# Charger.net
KiCad netlist of a schematic drawn in Altium Designer
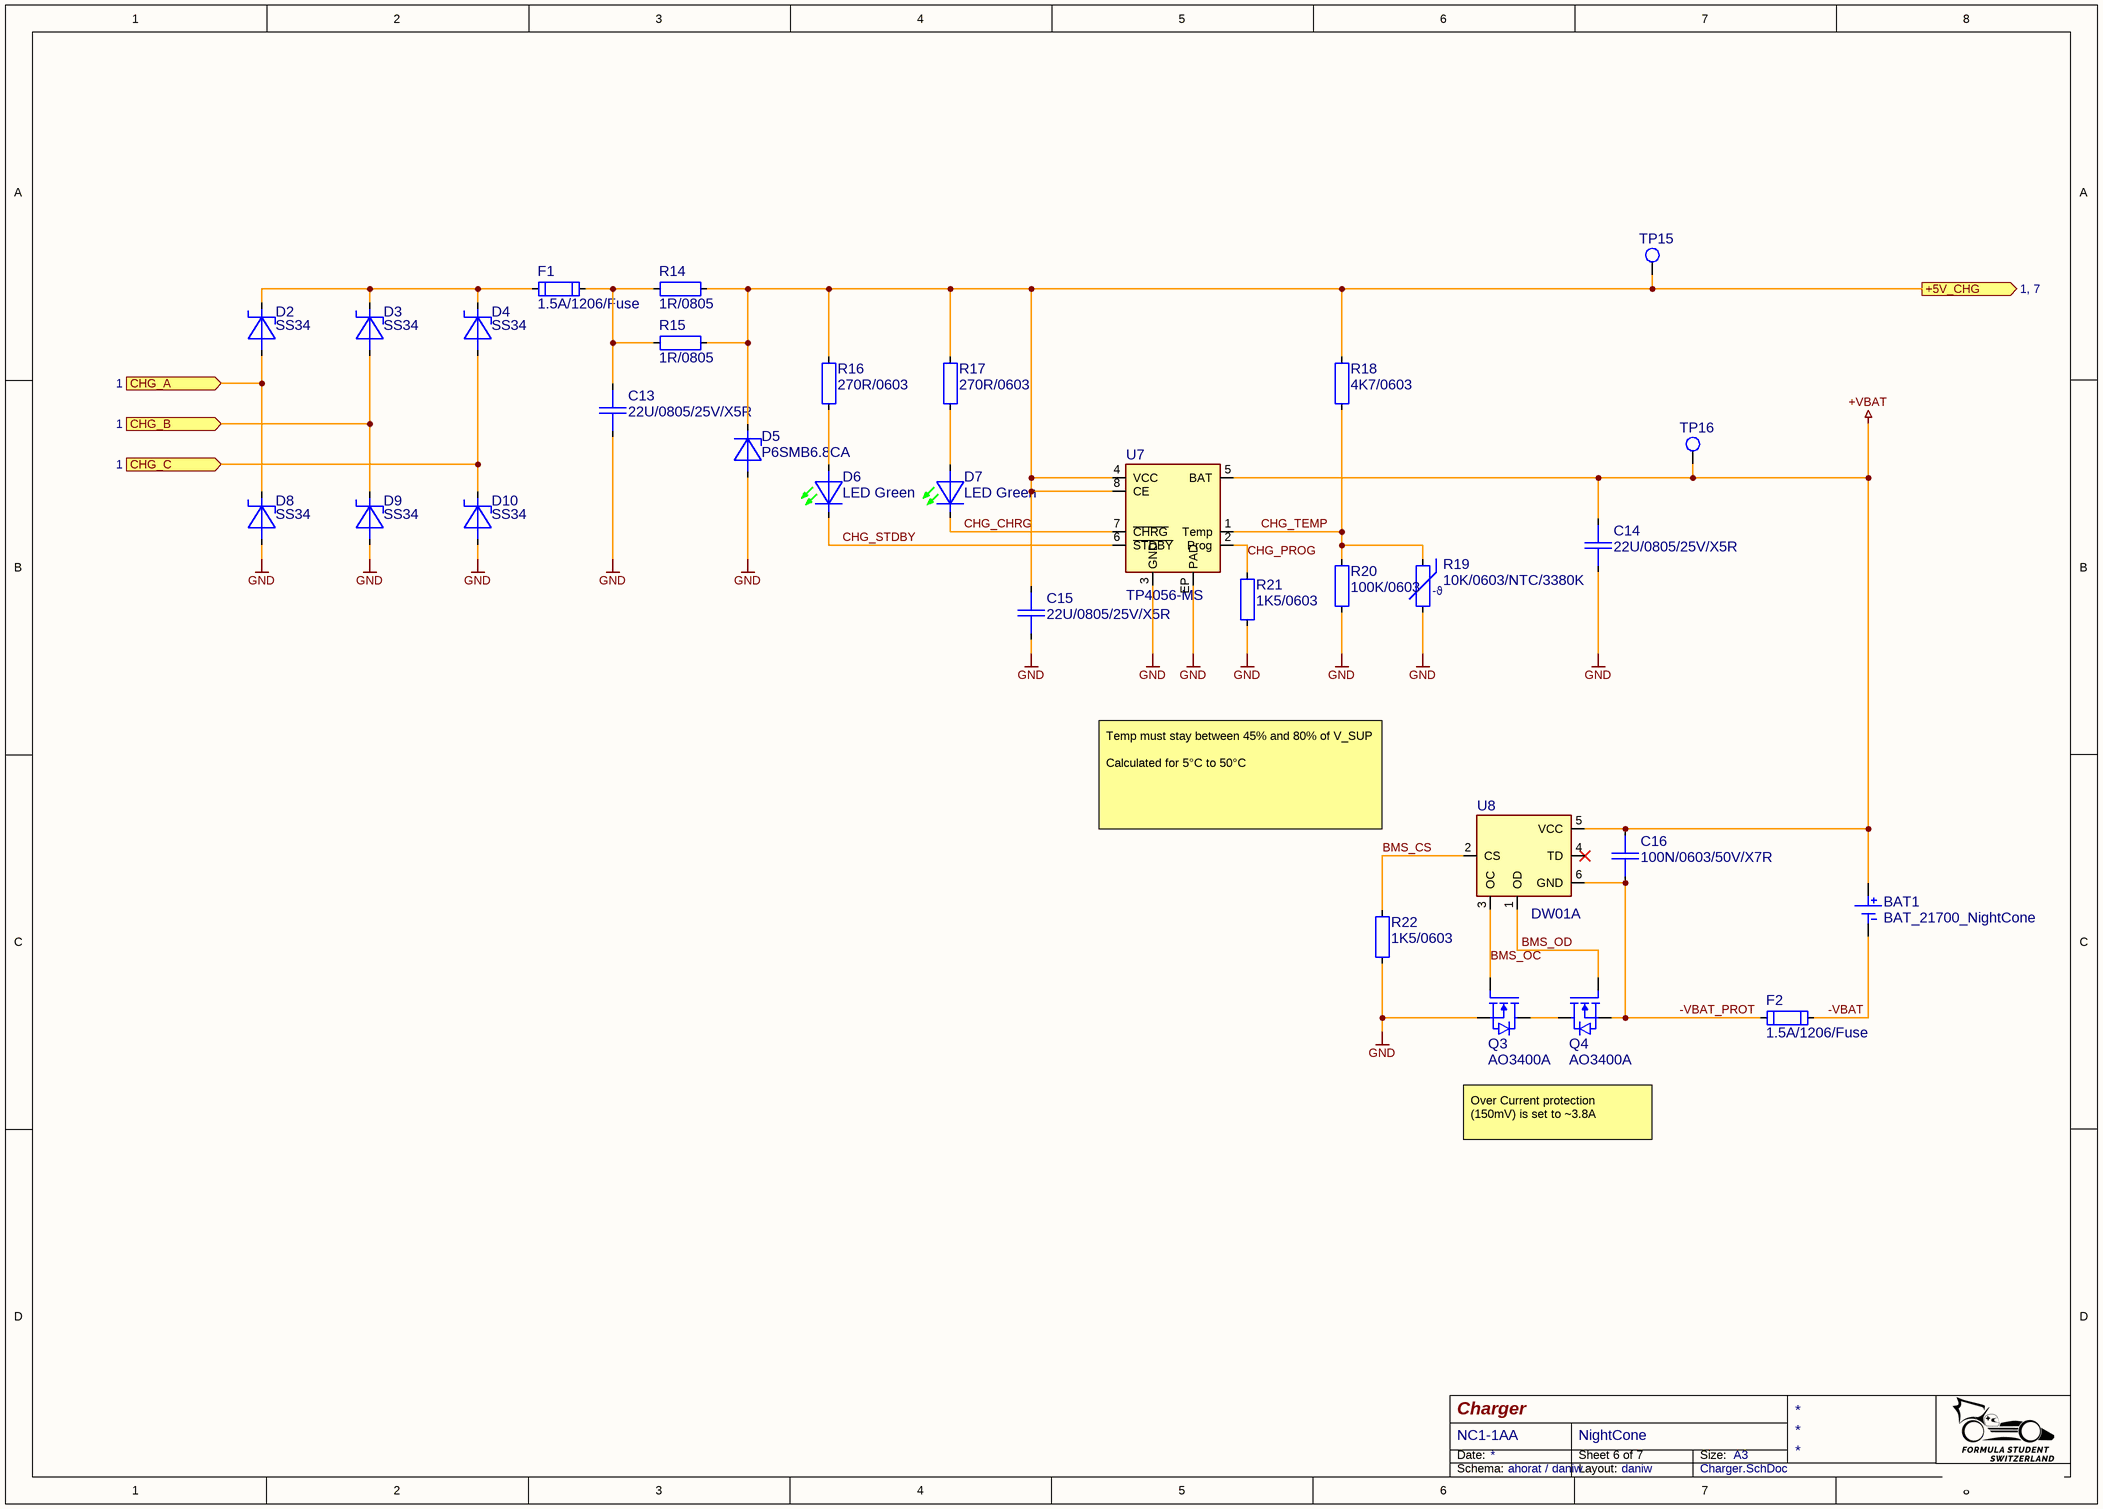
[diagram p0: Charger.SchDoc]

(export (version "E")
  (design (tool "Eeschema 10.0.6"))
  (components
    (comp (ref "BAT1")
      (value "BAT_21700_NightCone")
      (footprint "BAT-21700-NC")
      (description "21700 Battery cell for FSCH nightcone project")
      (fields (field (name "MANUFACTURER") "NONE"))
      (libsource (lib "daniw_altium_lib") (part "Battery_1"))
    )
    (comp (ref "C13")
      (value "22U/0805/25V/X5R")
      (footprint "CAP0805_X7R")
      (description "CAP SM 0805 22uF 25V X5R")
      (fields (field (name "MANUFACTURER") "GENERIC"))
      (libsource (lib "daniw_altium_lib") (part "C"))
    )
    (comp (ref "C14")
      (value "22U/0805/25V/X5R")
      (footprint "CAP0805_X7R")
      (description "CAP SM 0805 22uF 25V X5R")
      (fields (field (name "MANUFACTURER") "GENERIC"))
      (libsource (lib "daniw_altium_lib") (part "C"))
    )
    (comp (ref "C15")
      (value "22U/0805/25V/X5R")
      (footprint "CAP0805_X7R")
      (description "CAP SM 0805 22uF 25V X5R")
      (fields (field (name "MANUFACTURER") "GENERIC"))
      (libsource (lib "daniw_altium_lib") (part "C"))
    )
    (comp (ref "C16")
      (value "100N/0603/50V/X7R")
      (footprint "CAP0603_X7R")
      (description "CAP SM 0603 100nF 50V X7R")
      (fields (field (name "MANUFACTURER") "GENERIC"))
      (libsource (lib "daniw_altium_lib") (part "C"))
    )
    (comp (ref "D2")
      (value "SS34")
      (footprint "DIOM5226X230")
      (description "Si Shottky Diode 3A DO-214AC")
      (fields (field (name "MANUFACTURER") "GENERIC"))
      (libsource (lib "daniw_altium_lib") (part "D_Schottky"))
    )
    (comp (ref "D3")
      (value "SS34")
      (footprint "DIOM5226X230")
      (description "Si Shottky Diode 3A DO-214AC")
      (fields (field (name "MANUFACTURER") "GENERIC"))
      (libsource (lib "daniw_altium_lib") (part "D_Schottky"))
    )
    (comp (ref "D4")
      (value "SS34")
      (footprint "DIOM5226X230")
      (description "Si Shottky Diode 3A DO-214AC")
      (fields (field (name "MANUFACTURER") "GENERIC"))
      (libsource (lib "daniw_altium_lib") (part "D_Schottky"))
    )
    (comp (ref "D5")
      (value "P6SMB6.8CA")
      (footprint "DIOM5436X265")
      (description "10.5V 6.45V 5.8V SMB(DO-214AA) TVS")
      (fields (field (name "MANUFACTURER") "Littelfuse Inc."))
      (libsource (lib "daniw_altium_lib") (part "D_Zener"))
    )
    (comp (ref "D6")
      (value "LED Green")
      (footprint "LED0805_GREEN")
      (description "Generic LED Green 0805")
      (fields (field (name "PART NUMBER") "LED Green 0805") (field (name "MANUFACTURER") "GENERIC"))
      (libsource (lib "daniw_altium_lib") (part "LED_GREEN"))
    )
    (comp (ref "D7")
      (value "LED Green")
      (footprint "LED0805_GREEN")
      (description "Generic LED Green 0805")
      (fields (field (name "PART NUMBER") "LED Green 0805") (field (name "MANUFACTURER") "GENERIC"))
      (libsource (lib "daniw_altium_lib") (part "LED_GREEN"))
    )
    (comp (ref "D8")
      (value "SS34")
      (footprint "DIOM5226X230")
      (description "Si Shottky Diode 3A DO-214AC")
      (fields (field (name "MANUFACTURER") "GENERIC"))
      (libsource (lib "daniw_altium_lib") (part "D_Schottky"))
    )
    (comp (ref "D9")
      (value "SS34")
      (footprint "DIOM5226X230")
      (description "Si Shottky Diode 3A DO-214AC")
      (fields (field (name "MANUFACTURER") "GENERIC"))
      (libsource (lib "daniw_altium_lib") (part "D_Schottky"))
    )
    (comp (ref "D10")
      (value "SS34")
      (footprint "DIOM5226X230")
      (description "Si Shottky Diode 3A DO-214AC")
      (fields (field (name "MANUFACTURER") "GENERIC"))
      (libsource (lib "daniw_altium_lib") (part "D_Schottky"))
    )
    (comp (ref "F1")
      (value "1.5A/1206/Fuse")
      (footprint "Fuse1206-0.55-WW")
      (description "Multifuse 1206 1.5A")
      (fields (field (name "MANUFACTURER") "GENERIC"))
      (libsource (lib "daniw_altium_lib") (part "Fuse"))
    )
    (comp (ref "F2")
      (value "1.5A/1206/Fuse")
      (footprint "Fuse1206-0.55-WW")
      (description "Multifuse 1206 1.5A")
      (fields (field (name "MANUFACTURER") "GENERIC"))
      (libsource (lib "daniw_altium_lib") (part "Fuse"))
    )
    (comp (ref "Q3")
      (value "AO3400A")
      (footprint "SOT2395P280X125-3-SE")
      (description "30V N-Channel MOSFET")
      (fields (field (name "MANUFACTURER") "Alpha & Omega Semiconductor"))
      (libsource (lib "daniw_altium_lib") (part "MOSFET N_SOT23"))
    )
    (comp (ref "Q4")
      (value "AO3400A")
      (footprint "SOT2395P280X125-3-SE")
      (description "30V N-Channel MOSFET")
      (fields (field (name "MANUFACTURER") "Alpha & Omega Semiconductor"))
      (libsource (lib "daniw_altium_lib") (part "MOSFET N_SOT23"))
    )
    (comp (ref "R14")
      (value "1R/0805")
      (footprint "R0805-0.50-WW")
      (description "RES SM 0805 1R")
      (fields (field (name "MANUFACTURER") "GENERIC"))
      (libsource (lib "daniw_altium_lib") (part "R"))
    )
    (comp (ref "R15")
      (value "1R/0805")
      (footprint "R0805-0.50-WW")
      (description "RES SM 0805 1R")
      (fields (field (name "MANUFACTURER") "GENERIC"))
      (libsource (lib "daniw_altium_lib") (part "R"))
    )
    (comp (ref "R16")
      (value "270R/0603")
      (footprint "R0603-0.40-WW")
      (description "RES SM 0603 270R")
      (fields (field (name "MANUFACTURER") "GENERIC"))
      (libsource (lib "daniw_altium_lib") (part "R"))
    )
    (comp (ref "R17")
      (value "270R/0603")
      (footprint "R0603-0.40-WW")
      (description "RES SM 0603 270R")
      (fields (field (name "MANUFACTURER") "GENERIC"))
      (libsource (lib "daniw_altium_lib") (part "R"))
    )
    (comp (ref "R18")
      (value "4K7/0603")
      (footprint "R0603-0.40-WW")
      (description "RES SM 0603 4K7")
      (fields (field (name "MANUFACTURER") "GENERIC"))
      (libsource (lib "daniw_altium_lib") (part "R"))
    )
    (comp (ref "R19")
      (value "10K/0603/NTC/3380K")
      (footprint "R0603-0.40-WW")
      (description "RES NTC SM 0603 10K")
      (fields (field (name "MANUFACTURER") "GENERIC"))
      (libsource (lib "daniw_altium_lib") (part "R_NTC"))
    )
    (comp (ref "R20")
      (value "100K/0603")
      (footprint "R0603-0.40-WW")
      (description "RES SM 0603 100K")
      (fields (field (name "MANUFACTURER") "GENERIC"))
      (libsource (lib "daniw_altium_lib") (part "R"))
    )
    (comp (ref "R21")
      (value "1K5/0603")
      (footprint "R0603-0.40-WW")
      (description "RES SM 0603 1K5")
      (fields (field (name "MANUFACTURER") "GENERIC"))
      (libsource (lib "daniw_altium_lib") (part "R"))
    )
    (comp (ref "R22")
      (value "1K5/0603")
      (footprint "R0603-0.40-WW")
      (description "RES SM 0603 1K5")
      (fields (field (name "MANUFACTURER") "GENERIC"))
      (libsource (lib "daniw_altium_lib") (part "R"))
    )
    (comp (ref "TP15")
      (value "TP_THD_1.5/0.8")
      (footprint "TP_THD_1.5/0.8")
      (description "THT Test Point 1.5/0.8mm")
      (fields (field (name "MANUFACTURER") "NONE"))
      (libsource (lib "daniw_altium_lib") (part "Testpoint"))
    )
    (comp (ref "TP16")
      (value "TP_THD_1.5/0.8")
      (footprint "TP_THD_1.5/0.8")
      (description "THT Test Point 1.5/0.8mm")
      (fields (field (name "MANUFACTURER") "NONE"))
      (libsource (lib "daniw_altium_lib") (part "Testpoint"))
    )
    (comp (ref "U7")
      (value "TP4056-MS")
      (footprint "SOP127P600X155-9-TH330x240-NW")
      (description "1A Standalone Linear Li-lon Battery Charger with Thermal Regulation in SOP-8")
      (fields (field (name "MANUFACTURER") "MSKSEMI"))
      (libsource (lib "daniw_altium_lib") (part "TP4056"))
    )
    (comp (ref "U8")
      (value "DW01A")
      (footprint "SOT2395P280X125-6-SW")
      (description "Single Cell Lithium-ion battery protection IC")
      (fields (field (name "MANUFACTURER") "PUOLOP"))
      (libsource (lib "daniw_altium_lib") (part "DW01A"))
    )
  )
  (nets
    (net (code "1") (name "+VBAT") (class "Default")
      (node (ref "BAT1") (pin "1") (pinfunction "+_1") (pintype "passive"))
      (node (ref "C14") (pin "1") (pinfunction "1_1") (pintype "passive"))
      (node (ref "C16") (pin "1") (pinfunction "1_1") (pintype "passive"))
      (node (ref "TP16") (pin "1") (pinfunction "1_1") (pintype "passive"))
      (node (ref "U7") (pin "5") (pinfunction "BAT_5") (pintype "passive"))
      (node (ref "U8") (pin "5") (pinfunction "VCC_5") (pintype "passive"))
    )
    (net (code "2") (name "/+5V_CHG") (class "Default")
      (node (ref "C15") (pin "1") (pinfunction "1_1") (pintype "passive"))
      (node (ref "D5") (pin "1") (pinfunction "1_1") (pintype "passive"))
      (node (ref "R14") (pin "2") (pinfunction "2_2") (pintype "passive"))
      (node (ref "R15") (pin "2") (pinfunction "2_2") (pintype "passive"))
      (node (ref "R16") (pin "1") (pinfunction "1_1") (pintype "passive"))
      (node (ref "R17") (pin "1") (pinfunction "1_1") (pintype "passive"))
      (node (ref "R18") (pin "1") (pinfunction "1_1") (pintype "passive"))
      (node (ref "TP15") (pin "1") (pinfunction "1_1") (pintype "passive"))
      (node (ref "U7") (pin "4") (pinfunction "VCC_4") (pintype "passive"))
      (node (ref "U7") (pin "8") (pinfunction "CE_8") (pintype "passive"))
    )
    (net (code "3") (name "/-VBAT") (class "Default")
      (node (ref "BAT1") (pin "2") (pinfunction "-_2") (pintype "passive"))
      (node (ref "F2") (pin "1") (pinfunction "1_1") (pintype "passive"))
    )
    (net (code "4") (name "/-VBAT_PROT") (class "Default")
      (node (ref "C16") (pin "2") (pinfunction "2_2") (pintype "passive"))
      (node (ref "F2") (pin "2") (pinfunction "2_2") (pintype "passive"))
      (node (ref "Q4") (pin "2") (pinfunction "SOURCE_2") (pintype "passive"))
      (node (ref "U8") (pin "6") (pinfunction "GND_6") (pintype "passive"))
    )
    (net (code "5") (name "/BMS_CS") (class "Default")
      (node (ref "R22") (pin "1") (pinfunction "1_1") (pintype "passive"))
      (node (ref "U8") (pin "2") (pinfunction "CS_2") (pintype "passive"))
    )
    (net (code "6") (name "/BMS_OC") (class "Default")
      (node (ref "Q3") (pin "1") (pinfunction "GATE_1") (pintype "passive"))
      (node (ref "U8") (pin "3") (pinfunction "OC_3") (pintype "passive"))
    )
    (net (code "7") (name "/BMS_OD") (class "Default")
      (node (ref "Q4") (pin "1") (pinfunction "GATE_1") (pintype "passive"))
      (node (ref "U8") (pin "1") (pinfunction "OD_1") (pintype "passive"))
    )
    (net (code "8") (name "/CHG_A") (class "Default")
      (node (ref "D2") (pin "2") (pinfunction "2_2") (pintype "passive"))
      (node (ref "D8") (pin "1") (pinfunction "1_1") (pintype "passive"))
    )
    (net (code "9") (name "/CHG_B") (class "Default")
      (node (ref "D3") (pin "2") (pinfunction "2_2") (pintype "passive"))
      (node (ref "D9") (pin "1") (pinfunction "1_1") (pintype "passive"))
    )
    (net (code "10") (name "/CHG_C") (class "Default")
      (node (ref "D10") (pin "1") (pinfunction "1_1") (pintype "passive"))
      (node (ref "D4") (pin "2") (pinfunction "2_2") (pintype "passive"))
    )
    (net (code "11") (name "/CHG_CHRG") (class "Default")
      (node (ref "D7") (pin "1") (pinfunction "1_1") (pintype "passive"))
      (node (ref "U7") (pin "7") (pinfunction "~{CHRG}_7") (pintype "passive"))
    )
    (net (code "12") (name "/CHG_PROG") (class "Default")
      (node (ref "R21") (pin "1") (pinfunction "1_1") (pintype "passive"))
      (node (ref "U7") (pin "2") (pinfunction "Prog_2") (pintype "passive"))
    )
    (net (code "13") (name "/CHG_STDBY") (class "Default")
      (node (ref "D6") (pin "1") (pinfunction "1_1") (pintype "passive"))
      (node (ref "U7") (pin "6") (pinfunction "~{STDBY}_6") (pintype "passive"))
    )
    (net (code "14") (name "/CHG_TEMP") (class "Default")
      (node (ref "R18") (pin "2") (pinfunction "2_2") (pintype "passive"))
      (node (ref "R19") (pin "1") (pinfunction "1_1") (pintype "passive"))
      (node (ref "R20") (pin "1") (pinfunction "1_1") (pintype "passive"))
      (node (ref "U7") (pin "1") (pinfunction "Temp_1") (pintype "passive"))
    )
    (net (code "15") (name "GND") (class "Default")
      (node (ref "C13") (pin "2") (pinfunction "2_2") (pintype "passive"))
      (node (ref "C14") (pin "2") (pinfunction "2_2") (pintype "passive"))
      (node (ref "C15") (pin "2") (pinfunction "2_2") (pintype "passive"))
      (node (ref "D10") (pin "2") (pinfunction "2_2") (pintype "passive"))
      (node (ref "D5") (pin "2") (pinfunction "2_2") (pintype "passive"))
      (node (ref "D8") (pin "2") (pinfunction "2_2") (pintype "passive"))
      (node (ref "D9") (pin "2") (pinfunction "2_2") (pintype "passive"))
      (node (ref "Q3") (pin "2") (pinfunction "SOURCE_2") (pintype "passive"))
      (node (ref "R19") (pin "2") (pinfunction "2_2") (pintype "passive"))
      (node (ref "R20") (pin "2") (pinfunction "2_2") (pintype "passive"))
      (node (ref "R21") (pin "2") (pinfunction "2_2") (pintype "passive"))
      (node (ref "R22") (pin "2") (pinfunction "2_2") (pintype "passive"))
      (node (ref "U7") (pin "3") (pinfunction "GND_3") (pintype "passive"))
      (node (ref "U7") (pin "EP") (pinfunction "PAD_EP") (pintype "passive"))
    )
    (net (code "16") (name "Net-(C13-Pad1)") (class "Default")
      (node (ref "C13") (pin "1") (pinfunction "1_1") (pintype "passive"))
      (node (ref "F1") (pin "2") (pinfunction "2_2") (pintype "passive"))
      (node (ref "R14") (pin "1") (pinfunction "1_1") (pintype "passive"))
      (node (ref "R15") (pin "1") (pinfunction "1_1") (pintype "passive"))
    )
    (net (code "17") (name "Net-(D2-Pad1)") (class "Default")
      (node (ref "D2") (pin "1") (pinfunction "1_1") (pintype "passive"))
      (node (ref "D3") (pin "1") (pinfunction "1_1") (pintype "passive"))
      (node (ref "D4") (pin "1") (pinfunction "1_1") (pintype "passive"))
      (node (ref "F1") (pin "1") (pinfunction "1_1") (pintype "passive"))
    )
    (net (code "18") (name "Net-(D6-Pad2)") (class "Default")
      (node (ref "D6") (pin "2") (pinfunction "2_2") (pintype "passive"))
      (node (ref "R16") (pin "2") (pinfunction "2_2") (pintype "passive"))
    )
    (net (code "19") (name "Net-(D7-Pad2)") (class "Default")
      (node (ref "D7") (pin "2") (pinfunction "2_2") (pintype "passive"))
      (node (ref "R17") (pin "2") (pinfunction "2_2") (pintype "passive"))
    )
    (net (code "20") (name "Net-(Q3-DRAIN)") (class "Default")
      (node (ref "Q3") (pin "3") (pinfunction "DRAIN_3") (pintype "passive"))
      (node (ref "Q4") (pin "3") (pinfunction "DRAIN_3") (pintype "passive"))
    )
    (net (code "21") (name "unconnected-(U8-TD-Pad4)") (class "Default")
      (node (ref "U8") (pin "4") (pinfunction "TD_4") (pintype "passive+no_connect"))
    )
  )
)
